# converter.net
KiCad netlist of a schematic drawn in EAGLE
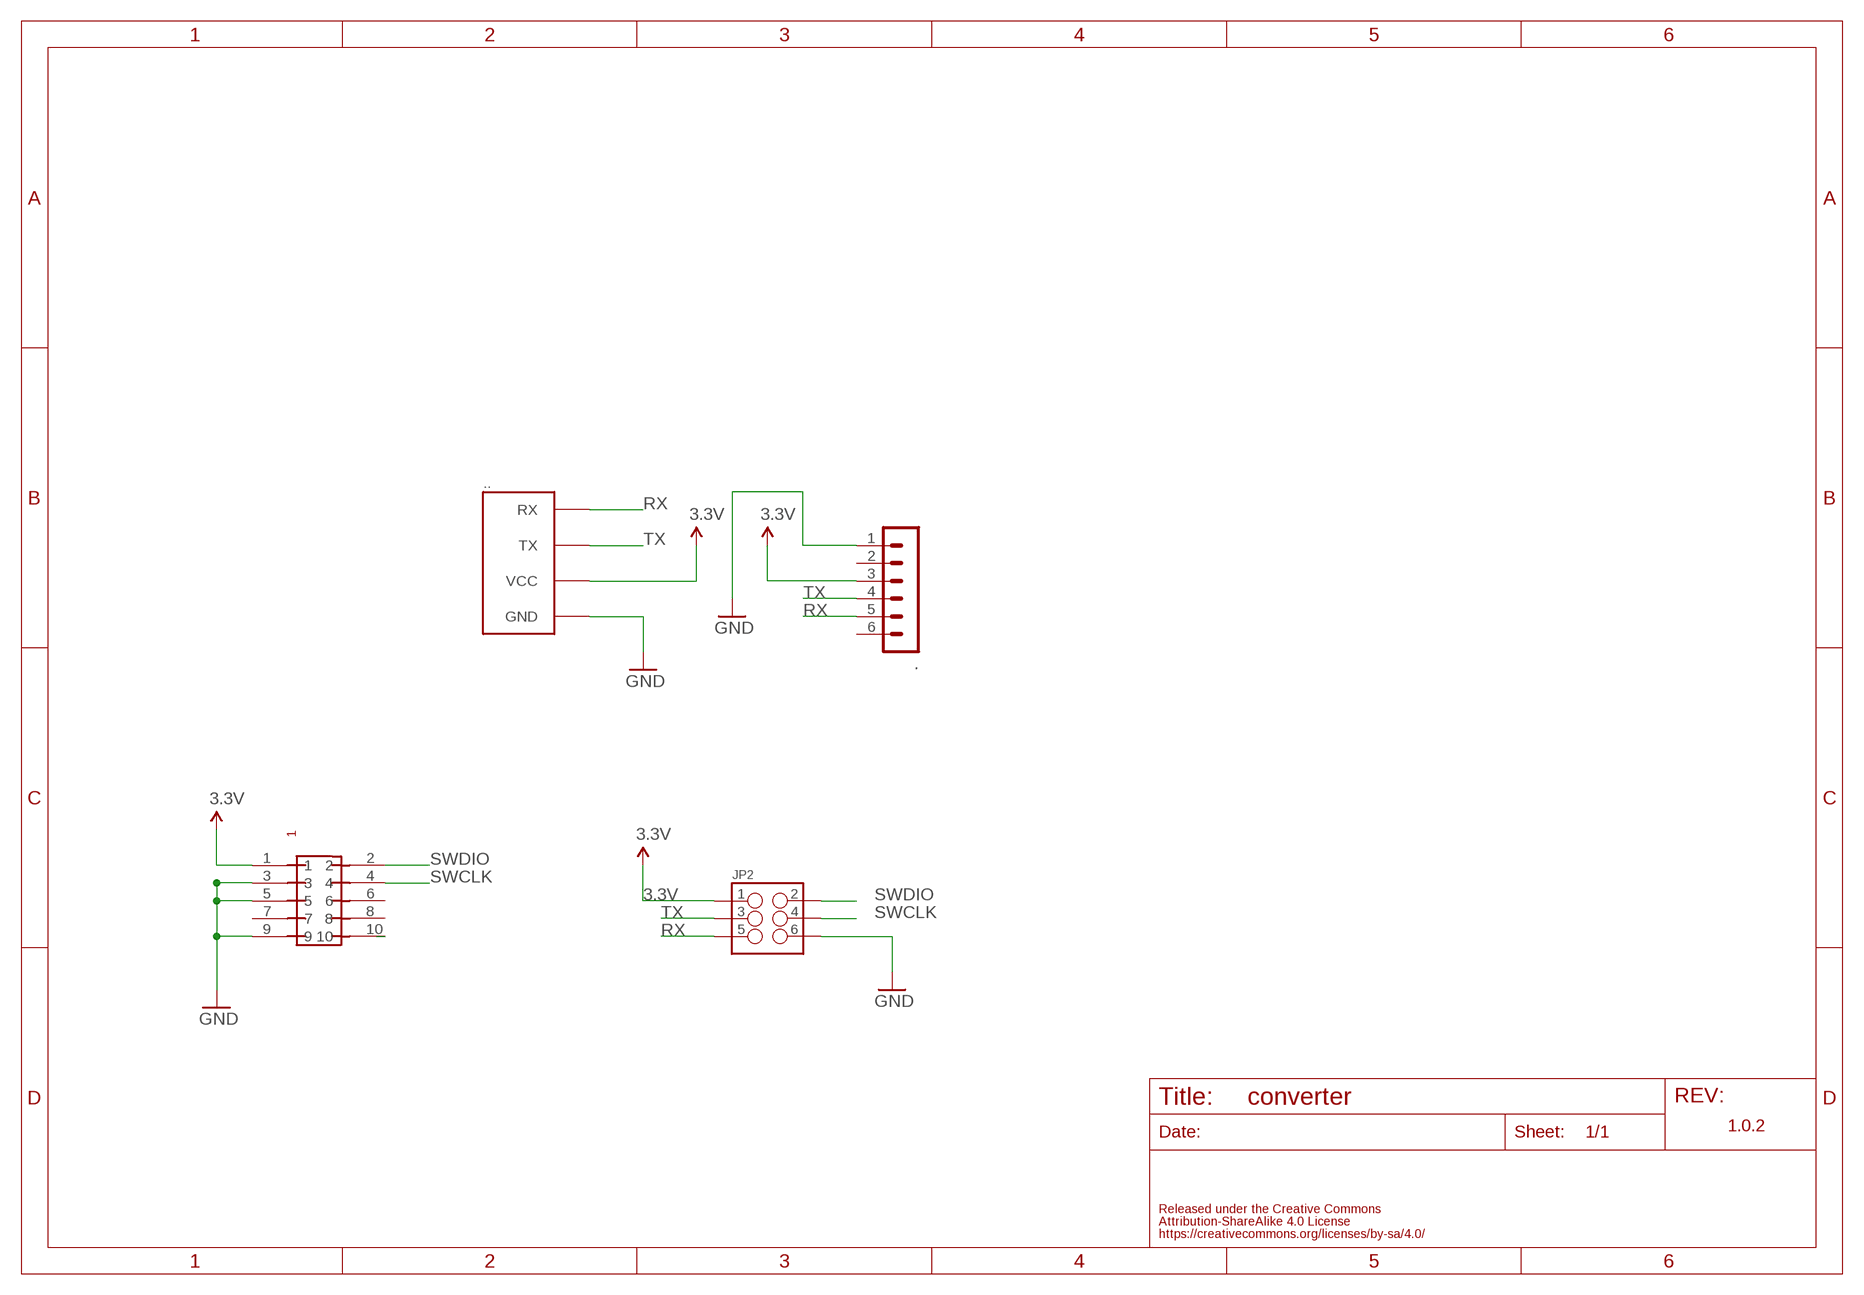
[diagram p0: schematic, sheet 1]

(export (version "E")
  (design (tool "Eeschema 10.0.6"))
  (components
    (comp (ref ".")
      (value "MA06-1")
      (footprint "eagle-import:MA06-1")
      (libsource (lib "eagle-import") (part "MA06-1"))
    )
    (comp (ref "..")
      (value "FABO_BRICK_SERIAL-S04B-PASK-2")
      (footprint "eagle-import:FABO_BRICK_SERIAL_S04B-PASK-2")
      (libsource (lib "eagle-import") (part "FABO_BRICK_SERIAL-S04B-PASK-2"))
    )
    (comp (ref "JP2")
      (value "M03X2")
      (footprint "eagle-import:2X3-SHROUDED")
      (libsource (lib "eagle-import") (part "M03X2"))
    )
    (comp (ref "U$5")
      (value "PIN-HEADER-SMT(1.27MM)2X5")
      (footprint "eagle-import:PIN-HEADER-SMT(1.27MM)2X5")
      (libsource (lib "eagle-import") (part "PIN-HEADER-SMT(1.27MM)2X5"))
    )
  )
  (nets
    (net (code "1") (name "/RX") (class "Default")
      (node (ref ".") (pin "5") (pinfunction "5_5") (pintype "passive"))
      (node (ref "..") (pin "RX") (pinfunction "RX_RX") (pintype "bidirectional"))
      (node (ref "JP2") (pin "5") (pinfunction "5_5") (pintype "bidirectional"))
    )
    (net (code "2") (name "/SWCLK") (class "Default")
      (node (ref "JP2") (pin "4") (pinfunction "4_4") (pintype "bidirectional"))
      (node (ref "U$5") (pin "4") (pinfunction "4_4") (pintype "bidirectional"))
    )
    (net (code "3") (name "/SWDIO") (class "Default")
      (node (ref "JP2") (pin "2") (pinfunction "2_2") (pintype "bidirectional"))
      (node (ref "U$5") (pin "2") (pinfunction "2_2") (pintype "bidirectional"))
    )
    (net (code "4") (name "/TX") (class "Default")
      (node (ref ".") (pin "4") (pinfunction "4_4") (pintype "passive"))
      (node (ref "..") (pin "TX") (pinfunction "TX_TX") (pintype "bidirectional"))
      (node (ref "JP2") (pin "3") (pinfunction "3_3") (pintype "bidirectional"))
    )
    (net (code "5") (name "3.3V") (class "Default")
      (node (ref ".") (pin "3") (pinfunction "3_3") (pintype "passive"))
      (node (ref "..") (pin "VCC") (pinfunction "VCC_VCC") (pintype "bidirectional"))
      (node (ref "JP2") (pin "1") (pinfunction "1_1") (pintype "bidirectional"))
      (node (ref "U$5") (pin "1") (pinfunction "1_1") (pintype "bidirectional"))
    )
    (net (code "6") (name "GND") (class "Default")
      (node (ref ".") (pin "1") (pinfunction "1_1") (pintype "passive"))
      (node (ref "..") (pin "GND") (pinfunction "GND_GND") (pintype "bidirectional"))
      (node (ref "JP2") (pin "6") (pinfunction "6_6") (pintype "bidirectional"))
      (node (ref "U$5") (pin "3") (pinfunction "3_3") (pintype "bidirectional"))
      (node (ref "U$5") (pin "5") (pinfunction "5_5") (pintype "bidirectional"))
      (node (ref "U$5") (pin "9") (pinfunction "9_9") (pintype "bidirectional"))
    )
    (net (code "7") (name "unconnected-(.-Pad2)") (class "Default")
      (node (ref ".") (pin "2") (pinfunction "2_2") (pintype "passive"))
    )
    (net (code "8") (name "unconnected-(.-Pad6)") (class "Default")
      (node (ref ".") (pin "6") (pinfunction "6_6") (pintype "passive"))
    )
    (net (code "9") (name "unconnected-(U$5-Pad6)") (class "Default")
      (node (ref "U$5") (pin "6") (pinfunction "6_6") (pintype "bidirectional"))
    )
    (net (code "10") (name "unconnected-(U$5-Pad7)") (class "Default")
      (node (ref "U$5") (pin "7") (pinfunction "7_7") (pintype "bidirectional"))
    )
    (net (code "11") (name "unconnected-(U$5-Pad8)") (class "Default")
      (node (ref "U$5") (pin "8") (pinfunction "8_8") (pintype "bidirectional"))
    )
    (net (code "12") (name "unconnected-(U$5-Pad10)") (class "Default")
      (node (ref "U$5") (pin "10") (pinfunction "10_10") (pintype "bidirectional"))
    )
  )
)
